# reader.net
KiCad netlist of a schematic drawn in EAGLE
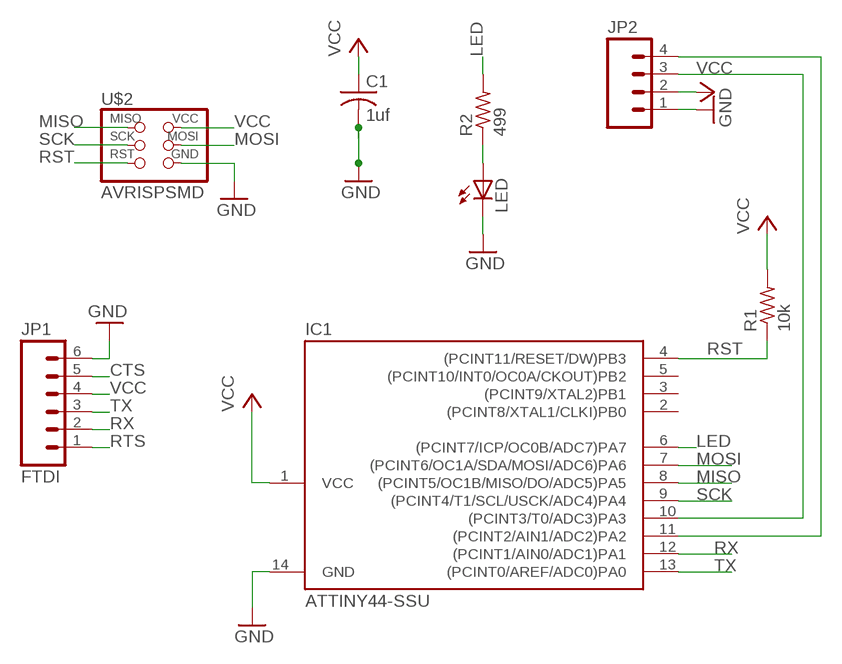
[diagram p0: schematic, sheet 1]

(export (version "E")
  (design (tool "Eeschema 10.0.6"))
  (components
    (comp (ref "C1")
      (value "1uf")
      (footprint "eagle-import:C1206")
      (libsource (lib "eagle-import") (part "C-USC1206"))
    )
    (comp (ref "IC1")
      (value "ATTINY44-SSU")
      (footprint "eagle-import:SOIC14")
      (libsource (lib "eagle-import") (part "ATTINY44-SSU"))
    )
    (comp (ref "JP1")
      (value "FTDI")
      (footprint "eagle-import:1X06-SMD")
      (libsource (lib "eagle-import") (part "M06SMD"))
    )
    (comp (ref "JP2")
      (value "M04LONGPADS")
      (footprint "eagle-import:1X04_LONGPADS")
      (libsource (lib "eagle-import") (part "M04LONGPADS"))
    )
    (comp (ref "LED")
      (value "LEDSMT1206")
      (footprint "eagle-import:1206")
      (libsource (lib "eagle-import") (part "LEDSMT1206"))
    )
    (comp (ref "R1")
      (value "10k")
      (footprint "eagle-import:R1206")
      (libsource (lib "eagle-import") (part "R-US_R1206"))
    )
    (comp (ref "R2")
      (value "499")
      (footprint "eagle-import:R1206")
      (libsource (lib "eagle-import") (part "R-US_R1206"))
    )
    (comp (ref "U$2")
      (value "AVRISPSMD")
      (footprint "eagle-import:2X03SMD")
      (libsource (lib "eagle-import") (part "AVRISPSMD"))
    )
  )
  (nets
    (net (code "1") (name "/CTS") (class "Default")
      (node (ref "JP1") (pin "5") (pinfunction "5_5") (pintype "passive"))
    )
    (net (code "2") (name "/LED") (class "Default")
      (node (ref "IC1") (pin "6") (pinfunction "(PCINT7/ICP/OC0B/ADC7)PA7_6") (pintype "bidirectional"))
      (node (ref "R2") (pin "2") (pinfunction "2_2") (pintype "passive"))
    )
    (net (code "3") (name "/MISO") (class "Default")
      (node (ref "IC1") (pin "8") (pinfunction "(PCINT5/OC1B/MISO/DO/ADC5)PA5_8") (pintype "bidirectional"))
      (node (ref "U$2") (pin "1") (pinfunction "MISO_1") (pintype "passive"))
    )
    (net (code "4") (name "/MOSI") (class "Default")
      (node (ref "IC1") (pin "7") (pinfunction "(PCINT6/OC1A/SDA/MOSI/ADC6)PA6_7") (pintype "bidirectional"))
      (node (ref "U$2") (pin "4") (pinfunction "MOSI_4") (pintype "passive"))
    )
    (net (code "5") (name "/RST") (class "Default")
      (node (ref "IC1") (pin "4") (pinfunction "(PCINT11/RESET/DW)PB3_4") (pintype "bidirectional"))
      (node (ref "R1") (pin "1") (pinfunction "1_1") (pintype "passive"))
      (node (ref "U$2") (pin "5") (pinfunction "RST_5") (pintype "passive"))
    )
    (net (code "6") (name "/RTS") (class "Default")
      (node (ref "JP1") (pin "1") (pinfunction "1_1") (pintype "passive"))
    )
    (net (code "7") (name "/RX") (class "Default")
      (node (ref "IC1") (pin "12") (pinfunction "(PCINT1/AIN0/ADC1)PA1_12") (pintype "bidirectional"))
      (node (ref "JP1") (pin "2") (pinfunction "2_2") (pintype "passive"))
    )
    (net (code "8") (name "/SCK") (class "Default")
      (node (ref "IC1") (pin "9") (pinfunction "(PCINT4/T1/SCL/USCK/ADC4)PA4_9") (pintype "bidirectional"))
      (node (ref "U$2") (pin "3") (pinfunction "SCK_3") (pintype "passive"))
    )
    (net (code "9") (name "/TX") (class "Default")
      (node (ref "IC1") (pin "13") (pinfunction "(PCINT0/AREF/ADC0)PA0_13") (pintype "bidirectional"))
      (node (ref "JP1") (pin "3") (pinfunction "3_3") (pintype "passive"))
    )
    (net (code "10") (name "GND") (class "Default")
      (node (ref "C1") (pin "2") (pinfunction "2_2") (pintype "passive"))
      (node (ref "IC1") (pin "14") (pinfunction "GND_14") (pintype "power_in"))
      (node (ref "JP1") (pin "6") (pinfunction "6_6") (pintype "passive"))
      (node (ref "JP2") (pin "1") (pinfunction "1_1") (pintype "passive"))
      (node (ref "LED") (pin "C") (pinfunction "C_C") (pintype "passive"))
      (node (ref "U$2") (pin "6") (pinfunction "GND_6") (pintype "passive"))
    )
    (net (code "11") (name "Net-(IC1-(PCINT2{slash}AIN1{slash}ADC2)PA2)") (class "Default")
      (node (ref "IC1") (pin "11") (pinfunction "(PCINT2/AIN1/ADC2)PA2_11") (pintype "bidirectional"))
      (node (ref "JP2") (pin "4") (pinfunction "4_4") (pintype "passive"))
    )
    (net (code "12") (name "Net-(IC1-(PCINT3{slash}T0{slash}ADC3)PA3)") (class "Default")
      (node (ref "IC1") (pin "10") (pinfunction "(PCINT3/T0/ADC3)PA3_10") (pintype "bidirectional"))
      (node (ref "JP2") (pin "3") (pinfunction "3_3") (pintype "passive"))
    )
    (net (code "13") (name "Net-(LED-PadA)") (class "Default")
      (node (ref "LED") (pin "A") (pinfunction "A_A") (pintype "passive"))
      (node (ref "R2") (pin "1") (pinfunction "1_1") (pintype "passive"))
    )
    (net (code "14") (name "VCC") (class "Default")
      (node (ref "C1") (pin "1") (pinfunction "1_1") (pintype "passive"))
      (node (ref "IC1") (pin "1") (pinfunction "VCC_1") (pintype "power_in"))
      (node (ref "JP1") (pin "4") (pinfunction "4_4") (pintype "passive"))
      (node (ref "JP2") (pin "2") (pinfunction "2_2") (pintype "passive"))
      (node (ref "R1") (pin "2") (pinfunction "2_2") (pintype "passive"))
      (node (ref "U$2") (pin "2") (pinfunction "VCC_2") (pintype "passive"))
    )
    (net (code "15") (name "unconnected-(IC1-(PCINT8{slash}XTAL1{slash}CLKI)PB0-Pad2)") (class "Default")
      (node (ref "IC1") (pin "2") (pinfunction "(PCINT8/XTAL1/CLKI)PB0_2") (pintype "bidirectional"))
    )
    (net (code "16") (name "unconnected-(IC1-(PCINT9{slash}XTAL2)PB1-Pad3)") (class "Default")
      (node (ref "IC1") (pin "3") (pinfunction "(PCINT9/XTAL2)PB1_3") (pintype "bidirectional"))
    )
    (net (code "17") (name "unconnected-(IC1-(PCINT10{slash}INT0{slash}OC0A{slash}CKOUT)PB2-Pad5)") (class "Default")
      (node (ref "IC1") (pin "5") (pinfunction "(PCINT10/INT0/OC0A/CKOUT)PB2_5") (pintype "bidirectional"))
    )
  )
)
